# remote.net
KiCad netlist of a schematic drawn in EAGLE
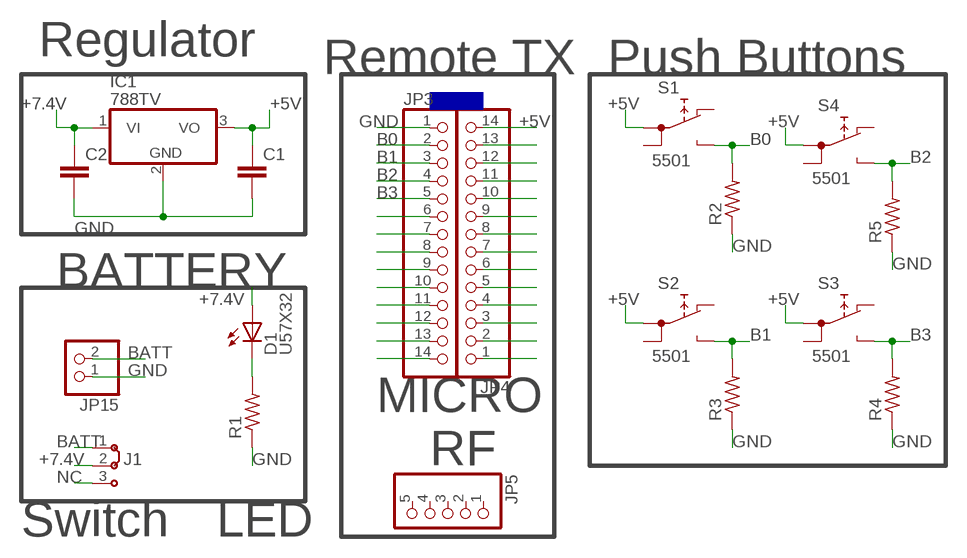
[diagram p0: schematic, sheet 1]

(export (version "E")
  (design (tool "Eeschema 10.0.6"))
  (components
    (comp (ref "C1")
      (value "C2,5-3")
      (footprint "eagle-import:C2.5-3")
      (libsource (lib "eagle-import") (part "C2,5-3"))
    )
    (comp (ref "C2")
      (value "C2,5-3")
      (footprint "eagle-import:C2.5-3")
      (libsource (lib "eagle-import") (part "C2,5-3"))
    )
    (comp (ref "D1")
      (value "U57X32")
      (footprint "eagle-import:U57X32")
      (libsource (lib "eagle-import") (part "U57X32"))
    )
    (comp (ref "IC1")
      (value "788TV")
      (footprint "eagle-import:TO220V")
      (libsource (lib "eagle-import") (part "78TV8"))
    )
    (comp (ref "J1")
      (value "J2X2MM")
      (footprint "eagle-import:04C")
      (libsource (lib "eagle-import") (part "J2X2MM"))
    )
    (comp (ref "JP3")
      (value "PINHD-1X14")
      (footprint "eagle-import:1X14")
      (libsource (lib "eagle-import") (part "PINHD-1X14"))
    )
    (comp (ref "JP4")
      (value "PINHD-1X14")
      (footprint "eagle-import:1X14")
      (libsource (lib "eagle-import") (part "PINHD-1X14"))
    )
    (comp (ref "JP5")
      (value "PINHD-1X5")
      (footprint "eagle-import:1X05")
      (libsource (lib "eagle-import") (part "PINHD-1X5"))
    )
    (comp (ref "JP15")
      (value "PINHD-1X2")
      (footprint "eagle-import:1X02")
      (libsource (lib "eagle-import") (part "PINHD-1X2"))
    )
    (comp (ref "R1")
      (value "R-US_0204/2V")
      (footprint "eagle-import:0204V")
      (libsource (lib "eagle-import") (part "R-US_0204/2V"))
    )
    (comp (ref "R2")
      (value "R-US_0204/2V")
      (footprint "eagle-import:0204V")
      (libsource (lib "eagle-import") (part "R-US_0204/2V"))
    )
    (comp (ref "R3")
      (value "R-US_0204/2V")
      (footprint "eagle-import:0204V")
      (libsource (lib "eagle-import") (part "R-US_0204/2V"))
    )
    (comp (ref "R4")
      (value "R-US_0204/2V")
      (footprint "eagle-import:0204V")
      (libsource (lib "eagle-import") (part "R-US_0204/2V"))
    )
    (comp (ref "R5")
      (value "R-US_0204/2V")
      (footprint "eagle-import:0204V")
      (libsource (lib "eagle-import") (part "R-US_0204/2V"))
    )
    (comp (ref "S1")
      (value "5501")
      (footprint "eagle-import:5501")
      (libsource (lib "eagle-import") (part "55?01"))
    )
    (comp (ref "S2")
      (value "5501")
      (footprint "eagle-import:5501")
      (libsource (lib "eagle-import") (part "55?01"))
    )
    (comp (ref "S3")
      (value "5501")
      (footprint "eagle-import:5501")
      (libsource (lib "eagle-import") (part "55?01"))
    )
    (comp (ref "S4")
      (value "5501")
      (footprint "eagle-import:5501")
      (libsource (lib "eagle-import") (part "55?01"))
    )
  )
  (nets
    (net (code "1") (name "/+5V") (class "Default")
      (node (ref "C1") (pin "1") (pinfunction "1_1") (pintype "passive"))
      (node (ref "IC1") (pin "3") (pinfunction "VO_3") (pintype "passive"))
      (node (ref "JP4") (pin "14") (pinfunction "14_14") (pintype "passive"))
      (node (ref "S1") (pin "1A") (pinfunction "1A_1A") (pintype "passive"))
      (node (ref "S2") (pin "1A") (pinfunction "1A_1A") (pintype "passive"))
      (node (ref "S3") (pin "1A") (pinfunction "1A_1A") (pintype "passive"))
      (node (ref "S4") (pin "1A") (pinfunction "1A_1A") (pintype "passive"))
    )
    (net (code "2") (name "/+7.4V") (class "Default")
      (node (ref "C2") (pin "1") (pinfunction "1_1") (pintype "passive"))
      (node (ref "D1") (pin "A") (pinfunction "A_A") (pintype "passive"))
      (node (ref "IC1") (pin "1") (pinfunction "VI_1") (pintype "input"))
      (node (ref "J1") (pin "2") (pinfunction "2_2") (pintype "passive"))
    )
    (net (code "3") (name "/B0") (class "Default")
      (node (ref "JP3") (pin "2") (pinfunction "2_2") (pintype "passive"))
      (node (ref "R2") (pin "2") (pinfunction "2_2") (pintype "passive"))
      (node (ref "S1") (pin "NO") (pinfunction "NO_NO") (pintype "passive"))
    )
    (net (code "4") (name "/B1") (class "Default")
      (node (ref "JP3") (pin "3") (pinfunction "3_3") (pintype "passive"))
      (node (ref "R3") (pin "2") (pinfunction "2_2") (pintype "passive"))
      (node (ref "S2") (pin "NO") (pinfunction "NO_NO") (pintype "passive"))
    )
    (net (code "5") (name "/B2") (class "Default")
      (node (ref "JP3") (pin "4") (pinfunction "4_4") (pintype "passive"))
      (node (ref "R5") (pin "2") (pinfunction "2_2") (pintype "passive"))
      (node (ref "S4") (pin "NO") (pinfunction "NO_NO") (pintype "passive"))
    )
    (net (code "6") (name "/B3") (class "Default")
      (node (ref "JP3") (pin "5") (pinfunction "5_5") (pintype "passive"))
      (node (ref "R4") (pin "2") (pinfunction "2_2") (pintype "passive"))
      (node (ref "S3") (pin "NO") (pinfunction "NO_NO") (pintype "passive"))
    )
    (net (code "7") (name "/BATT") (class "Default")
      (node (ref "J1") (pin "1") (pinfunction "1_1") (pintype "passive"))
      (node (ref "JP15") (pin "2") (pinfunction "2_2") (pintype "passive"))
    )
    (net (code "8") (name "/GND") (class "Default")
      (node (ref "C1") (pin "2") (pinfunction "2_2") (pintype "passive"))
      (node (ref "C2") (pin "2") (pinfunction "2_2") (pintype "passive"))
      (node (ref "IC1") (pin "2") (pinfunction "GND_2") (pintype "passive"))
      (node (ref "JP15") (pin "1") (pinfunction "1_1") (pintype "passive"))
      (node (ref "JP3") (pin "1") (pinfunction "1_1") (pintype "passive"))
      (node (ref "R1") (pin "1") (pinfunction "1_1") (pintype "passive"))
      (node (ref "R2") (pin "1") (pinfunction "1_1") (pintype "passive"))
      (node (ref "R3") (pin "1") (pinfunction "1_1") (pintype "passive"))
      (node (ref "R4") (pin "1") (pinfunction "1_1") (pintype "passive"))
      (node (ref "R5") (pin "1") (pinfunction "1_1") (pintype "passive"))
    )
    (net (code "9") (name "/NC") (class "Default")
      (node (ref "J1") (pin "3") (pinfunction "3_3") (pintype "passive"))
    )
    (net (code "10") (name "Net-(D1-C)") (class "Default")
      (node (ref "D1") (pin "K") (pinfunction "C_K") (pintype "passive"))
      (node (ref "R1") (pin "2") (pinfunction "2_2") (pintype "passive"))
    )
    (net (code "11") (name "unconnected-(JP3-Pad6)") (class "Default")
      (node (ref "JP3") (pin "6") (pinfunction "6_6") (pintype "passive"))
    )
    (net (code "12") (name "unconnected-(JP3-Pad7)") (class "Default")
      (node (ref "JP3") (pin "7") (pinfunction "7_7") (pintype "passive"))
    )
    (net (code "13") (name "unconnected-(JP3-Pad8)") (class "Default")
      (node (ref "JP3") (pin "8") (pinfunction "8_8") (pintype "passive"))
    )
    (net (code "14") (name "unconnected-(JP3-Pad9)") (class "Default")
      (node (ref "JP3") (pin "9") (pinfunction "9_9") (pintype "passive"))
    )
    (net (code "15") (name "unconnected-(JP3-Pad10)") (class "Default")
      (node (ref "JP3") (pin "10") (pinfunction "10_10") (pintype "passive"))
    )
    (net (code "16") (name "unconnected-(JP3-Pad11)") (class "Default")
      (node (ref "JP3") (pin "11") (pinfunction "11_11") (pintype "passive"))
    )
    (net (code "17") (name "unconnected-(JP3-Pad12)") (class "Default")
      (node (ref "JP3") (pin "12") (pinfunction "12_12") (pintype "passive"))
    )
    (net (code "18") (name "unconnected-(JP3-Pad13)") (class "Default")
      (node (ref "JP3") (pin "13") (pinfunction "13_13") (pintype "passive"))
    )
    (net (code "19") (name "unconnected-(JP3-Pad14)") (class "Default")
      (node (ref "JP3") (pin "14") (pinfunction "14_14") (pintype "passive"))
    )
    (net (code "20") (name "unconnected-(JP4-Pad1)") (class "Default")
      (node (ref "JP4") (pin "1") (pinfunction "1_1") (pintype "passive"))
    )
    (net (code "21") (name "unconnected-(JP4-Pad2)") (class "Default")
      (node (ref "JP4") (pin "2") (pinfunction "2_2") (pintype "passive"))
    )
    (net (code "22") (name "unconnected-(JP4-Pad3)") (class "Default")
      (node (ref "JP4") (pin "3") (pinfunction "3_3") (pintype "passive"))
    )
    (net (code "23") (name "unconnected-(JP4-Pad4)") (class "Default")
      (node (ref "JP4") (pin "4") (pinfunction "4_4") (pintype "passive"))
    )
    (net (code "24") (name "unconnected-(JP4-Pad5)") (class "Default")
      (node (ref "JP4") (pin "5") (pinfunction "5_5") (pintype "passive"))
    )
    (net (code "25") (name "unconnected-(JP4-Pad6)") (class "Default")
      (node (ref "JP4") (pin "6") (pinfunction "6_6") (pintype "passive"))
    )
    (net (code "26") (name "unconnected-(JP4-Pad7)") (class "Default")
      (node (ref "JP4") (pin "7") (pinfunction "7_7") (pintype "passive"))
    )
    (net (code "27") (name "unconnected-(JP4-Pad8)") (class "Default")
      (node (ref "JP4") (pin "8") (pinfunction "8_8") (pintype "passive"))
    )
    (net (code "28") (name "unconnected-(JP4-Pad9)") (class "Default")
      (node (ref "JP4") (pin "9") (pinfunction "9_9") (pintype "passive"))
    )
    (net (code "29") (name "unconnected-(JP4-Pad10)") (class "Default")
      (node (ref "JP4") (pin "10") (pinfunction "10_10") (pintype "passive"))
    )
    (net (code "30") (name "unconnected-(JP4-Pad11)") (class "Default")
      (node (ref "JP4") (pin "11") (pinfunction "11_11") (pintype "passive"))
    )
    (net (code "31") (name "unconnected-(JP4-Pad12)") (class "Default")
      (node (ref "JP4") (pin "12") (pinfunction "12_12") (pintype "passive"))
    )
    (net (code "32") (name "unconnected-(JP4-Pad13)") (class "Default")
      (node (ref "JP4") (pin "13") (pinfunction "13_13") (pintype "passive"))
    )
    (net (code "33") (name "unconnected-(JP5-Pad1)") (class "Default")
      (node (ref "JP5") (pin "1") (pinfunction "1_1") (pintype "passive"))
    )
    (net (code "34") (name "unconnected-(JP5-Pad2)") (class "Default")
      (node (ref "JP5") (pin "2") (pinfunction "2_2") (pintype "passive"))
    )
    (net (code "35") (name "unconnected-(JP5-Pad3)") (class "Default")
      (node (ref "JP5") (pin "3") (pinfunction "3_3") (pintype "passive"))
    )
    (net (code "36") (name "unconnected-(JP5-Pad4)") (class "Default")
      (node (ref "JP5") (pin "4") (pinfunction "4_4") (pintype "passive"))
    )
    (net (code "37") (name "unconnected-(JP5-Pad5)") (class "Default")
      (node (ref "JP5") (pin "5") (pinfunction "5_5") (pintype "passive"))
    )
    (net (code "38") (name "unconnected-(S1-Pad1B)") (class "Default")
      (node (ref "S1") (pin "1B") (pinfunction "1B_1B") (pintype "passive"))
    )
    (net (code "39") (name "unconnected-(S1-PadNC)") (class "Default")
      (node (ref "S1") (pin "NC") (pinfunction "NC_NC") (pintype "passive"))
    )
    (net (code "40") (name "unconnected-(S2-Pad1B)") (class "Default")
      (node (ref "S2") (pin "1B") (pinfunction "1B_1B") (pintype "passive"))
    )
    (net (code "41") (name "unconnected-(S2-PadNC)") (class "Default")
      (node (ref "S2") (pin "NC") (pinfunction "NC_NC") (pintype "passive"))
    )
    (net (code "42") (name "unconnected-(S3-Pad1B)") (class "Default")
      (node (ref "S3") (pin "1B") (pinfunction "1B_1B") (pintype "passive"))
    )
    (net (code "43") (name "unconnected-(S3-PadNC)") (class "Default")
      (node (ref "S3") (pin "NC") (pinfunction "NC_NC") (pintype "passive"))
    )
    (net (code "44") (name "unconnected-(S4-Pad1B)") (class "Default")
      (node (ref "S4") (pin "1B") (pinfunction "1B_1B") (pintype "passive"))
    )
    (net (code "45") (name "unconnected-(S4-PadNC)") (class "Default")
      (node (ref "S4") (pin "NC") (pinfunction "NC_NC") (pintype "passive"))
    )
  )
)
